# T8105.net
KiCad netlist of a schematic drawn in Altium Designer
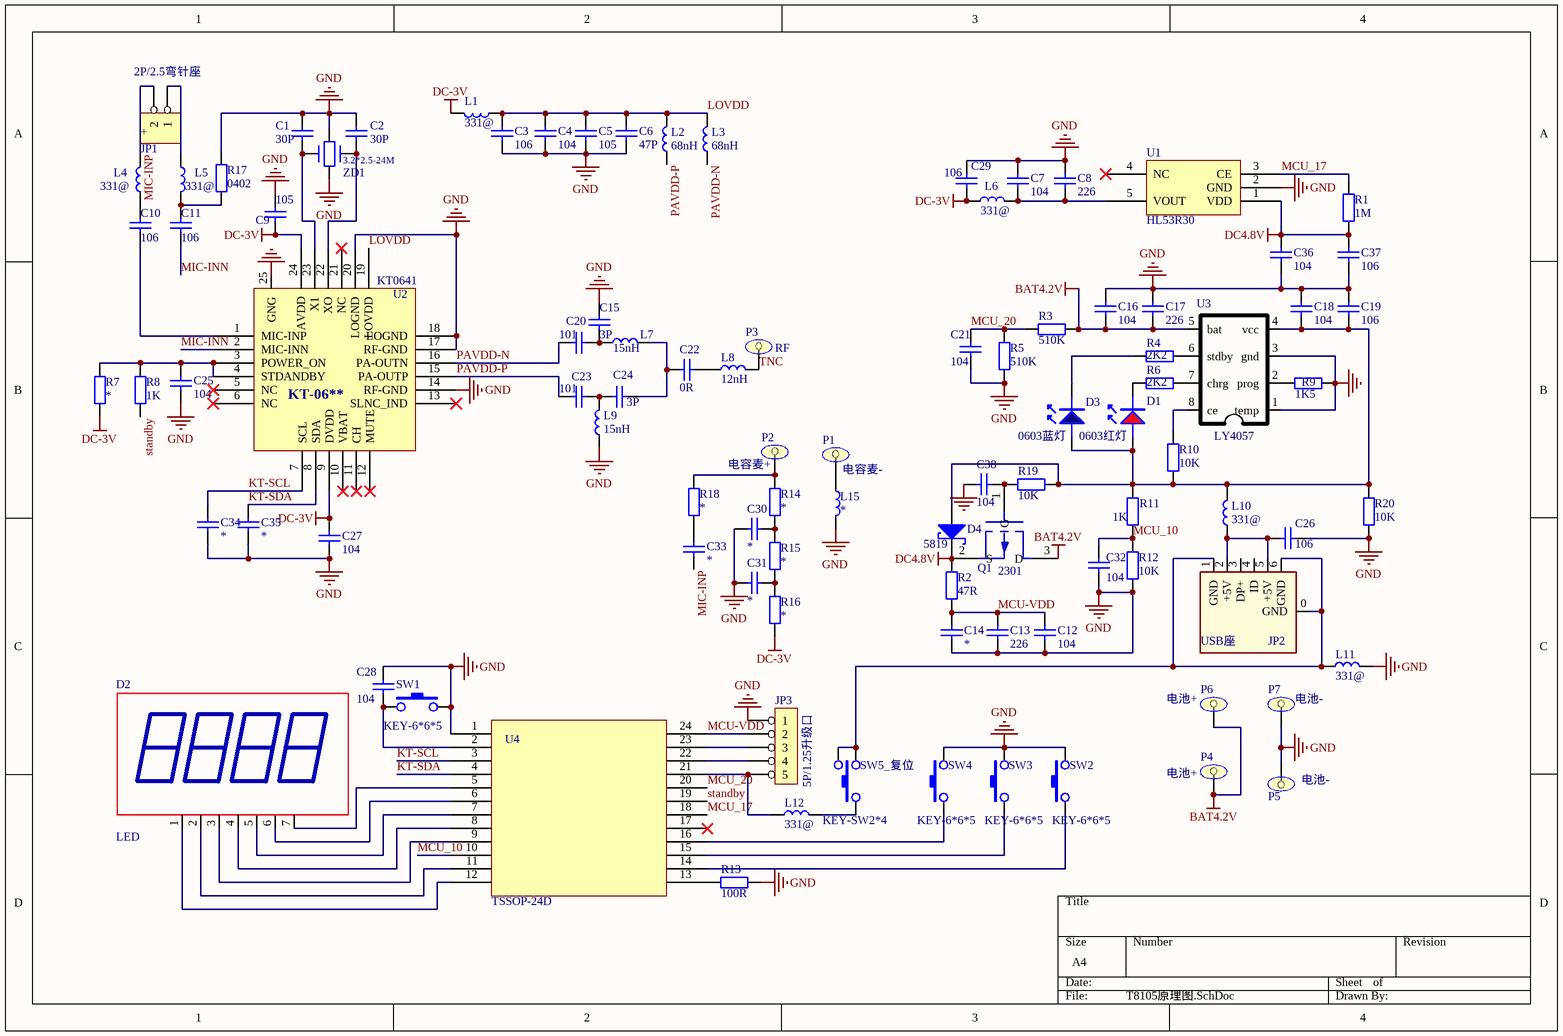
[diagram p0: T8105原理图.SchDoc]

(export (version "E")
  (design (tool "Eeschema 10.0.6"))
  (components
    (comp (ref "C1")
      (value "30P")
      (footprint "C0402")
      (description "贴片电容")
      (libsource (lib "CLR原理图封装库") (part "C0402"))
    )
    (comp (ref "C2")
      (value "30P")
      (footprint "C0402")
      (description "贴片电容")
      (libsource (lib "CLR原理图封装库") (part "C0402"))
    )
    (comp (ref "C3")
      (value "106")
      (footprint "C0603")
      (description "贴片电容")
      (libsource (lib "CLR原理图封装库") (part "C0603"))
    )
    (comp (ref "C4")
      (value "104")
      (footprint "C0402")
      (description "贴片电容")
      (libsource (lib "CLR原理图封装库") (part "C0402"))
    )
    (comp (ref "C5")
      (value "105")
      (footprint "C0402")
      (description "贴片电容")
      (libsource (lib "CLR原理图封装库") (part "C0402"))
    )
    (comp (ref "C6")
      (value "47P")
      (footprint "C0402")
      (description "贴片电容")
      (libsource (lib "CLR原理图封装库") (part "C0402"))
    )
    (comp (ref "C7")
      (value "104")
      (footprint "C0402")
      (description "贴片电容")
      (libsource (lib "CLR原理图封装库") (part "C0402"))
    )
    (comp (ref "C8")
      (value "226")
      (footprint "C0603")
      (description "贴片电容")
      (libsource (lib "CLR原理图封装库") (part "C0603"))
    )
    (comp (ref "C9")
      (value "105")
      (footprint "C0402")
      (description "贴片电容")
      (libsource (lib "CLR原理图封装库") (part "C0402"))
    )
    (comp (ref "C10")
      (value "106")
      (footprint "C0603")
      (description "贴片电容")
      (libsource (lib "CLR原理图封装库") (part "C0603"))
    )
    (comp (ref "C11")
      (value "106")
      (footprint "C0603")
      (description "贴片电容")
      (libsource (lib "CLR原理图封装库") (part "C0603"))
    )
    (comp (ref "C12")
      (value "104")
      (footprint "C0402")
      (description "贴片电容")
      (libsource (lib "CLR原理图封装库") (part "C0402"))
    )
    (comp (ref "C13")
      (value "226")
      (footprint "C0603")
      (description "贴片电容")
      (libsource (lib "CLR原理图封装库") (part "C0603"))
    )
    (comp (ref "C14")
      (value "*")
      (footprint "C1206")
      (description "贴片电容")
      (libsource (lib "CLR原理图封装库") (part "C1206"))
    )
    (comp (ref "C15")
      (value "3P")
      (footprint "C0402")
      (description "贴片电容")
      (libsource (lib "CLR原理图封装库") (part "C0402"))
    )
    (comp (ref "C16")
      (value "104")
      (footprint "C0402")
      (description "贴片电容")
      (libsource (lib "CLR原理图封装库") (part "C0402"))
    )
    (comp (ref "C17")
      (value "226")
      (footprint "C0603")
      (description "贴片电容")
      (libsource (lib "CLR原理图封装库") (part "C0603"))
    )
    (comp (ref "C18")
      (value "104")
      (footprint "C0402")
      (description "贴片电容")
      (libsource (lib "CLR原理图封装库") (part "C0402"))
    )
    (comp (ref "C19")
      (value "106")
      (footprint "C0603")
      (description "贴片电容")
      (libsource (lib "CLR原理图封装库") (part "C0603"))
    )
    (comp (ref "C20")
      (value "101")
      (footprint "C0402")
      (description "贴片电容")
      (libsource (lib "CLR原理图封装库") (part "C0402"))
    )
    (comp (ref "C21")
      (value "104")
      (footprint "C0402")
      (description "贴片电容")
      (libsource (lib "CLR原理图封装库") (part "C0402"))
    )
    (comp (ref "C22")
      (value "0R")
      (footprint "C0402")
      (description "贴片电容")
      (libsource (lib "CLR原理图封装库") (part "C0402"))
    )
    (comp (ref "C23")
      (value "101")
      (footprint "C0402")
      (description "贴片电容")
      (libsource (lib "CLR原理图封装库") (part "C0402"))
    )
    (comp (ref "C24")
      (value "3P")
      (footprint "C0402")
      (description "贴片电容")
      (libsource (lib "CLR原理图封装库") (part "C0402"))
    )
    (comp (ref "C25")
      (value "104")
      (footprint "C0402")
      (description "贴片电容")
      (libsource (lib "CLR原理图封装库") (part "C0402"))
    )
    (comp (ref "C26")
      (value "106")
      (footprint "C0603")
      (description "贴片电容")
      (libsource (lib "CLR原理图封装库") (part "C0603"))
    )
    (comp (ref "C27")
      (value "104")
      (footprint "C0402")
      (description "贴片电容")
      (libsource (lib "CLR原理图封装库") (part "C0402"))
    )
    (comp (ref "C28")
      (value "104")
      (footprint "C0402")
      (description "贴片电容")
      (libsource (lib "CLR原理图封装库") (part "C0402"))
    )
    (comp (ref "C29")
      (value "106")
      (footprint "C0603")
      (description "贴片电容")
      (libsource (lib "CLR原理图封装库") (part "C0603"))
    )
    (comp (ref "C30")
      (value "*")
      (footprint "C0603")
      (description "贴片电容")
      (libsource (lib "CLR原理图封装库") (part "C0603"))
    )
    (comp (ref "C31")
      (value "*")
      (footprint "C0603")
      (description "贴片电容")
      (libsource (lib "CLR原理图封装库") (part "C0603"))
    )
    (comp (ref "C32")
      (value "104")
      (footprint "C0402")
      (description "贴片电容")
      (libsource (lib "CLR原理图封装库") (part "C0402"))
    )
    (comp (ref "C33")
      (value "*")
      (footprint "C0603")
      (description "贴片电容")
      (libsource (lib "CLR原理图封装库") (part "C0603"))
    )
    (comp (ref "C34")
      (value "*")
      (footprint "C0402")
      (description "贴片电容")
      (libsource (lib "CLR原理图封装库") (part "C0402"))
    )
    (comp (ref "C35")
      (value "*")
      (footprint "C0402")
      (description "贴片电容")
      (libsource (lib "CLR原理图封装库") (part "C0402"))
    )
    (comp (ref "C36")
      (value "104")
      (footprint "C0402")
      (description "贴片电容")
      (libsource (lib "CLR原理图封装库") (part "C0402"))
    )
    (comp (ref "C37")
      (value "106")
      (footprint "C0603")
      (description "贴片电容")
      (libsource (lib "CLR原理图封装库") (part "C0603"))
    )
    (comp (ref "C38")
      (value "104")
      (footprint "C0402")
      (description "贴片电容")
      (libsource (lib "CLR原理图封装库") (part "C0402"))
    )
    (comp (ref "D1")
      (value "0603红灯")
      (footprint "LED-0603")
      (description "贴片LED")
      (libsource (lib "CLR原理图封装库") (part "LED-0603"))
    )
    (comp (ref "D2")
      (value "LED")
      (footprint "LED-15*16*7-7pin")
      (description "数码管")
      (libsource (lib "CLR原理图封装库") (part "LED-15*16/数码管"))
    )
    (comp (ref "D3")
      (value "0603蓝灯")
      (footprint "LED-0603")
      (description "贴片LED")
      (libsource (lib "CLR原理图封装库") (part "LED-0603_蓝"))
    )
    (comp (ref "D4")
      (value "5819")
      (footprint "SOD-123")
      (description "贴片肖特基二极管")
      (libsource (lib "CLR原理图封装库") (part "SOD-123"))
    )
    (comp (ref "JP1")
      (value "2P/2.5弯针座")
      (footprint "2P针座-2.54MM_弯针")
      (description "直插针座")
      (libsource (lib "CLR原理图封装库") (part "2P/2.5弯针座"))
    )
    (comp (ref "JP2")
      (value "USB座")
      (footprint "USB-TYPE-C3.1-6")
      (description "直插USB充电座")
      (libsource (lib "CLR原理图封装库") (part "USB-TYPE-C3.1-6"))
    )
    (comp (ref "JP3")
      (value "5P/1.25升级口")
      (footprint "5P插针-12.5MM")
      (description "直插插针")
      (libsource (lib "CLR原理图封装库") (part "5P/1.25插针"))
    )
    (comp (ref "L1")
      (value "331@")
      (footprint "L0402")
      (description "贴片电感")
      (libsource (lib "CLR原理图封装库") (part "L0402"))
    )
    (comp (ref "L2")
      (value "68nH")
      (footprint "L0603")
      (description "贴片电感")
      (libsource (lib "CLR原理图封装库") (part "L0603"))
    )
    (comp (ref "L3")
      (value "68nH")
      (footprint "L0402")
      (description "贴片电感")
      (libsource (lib "CLR原理图封装库") (part "L0402"))
    )
    (comp (ref "L4")
      (value "331@")
      (footprint "L0402")
      (description "贴片电感")
      (libsource (lib "CLR原理图封装库") (part "L0402"))
    )
    (comp (ref "L5")
      (value "331@")
      (footprint "L0402")
      (description "贴片电感")
      (libsource (lib "CLR原理图封装库") (part "L0402"))
    )
    (comp (ref "L6")
      (value "331@")
      (footprint "L0402")
      (description "贴片电感")
      (libsource (lib "CLR原理图封装库") (part "L0402"))
    )
    (comp (ref "L7")
      (value "15nH")
      (footprint "L0402")
      (description "贴片电感")
      (libsource (lib "CLR原理图封装库") (part "L0402"))
    )
    (comp (ref "L8")
      (value "12nH")
      (footprint "L0402")
      (description "贴片电感")
      (libsource (lib "CLR原理图封装库") (part "L0402"))
    )
    (comp (ref "L9")
      (value "15nH")
      (footprint "L0402")
      (description "贴片电感")
      (libsource (lib "CLR原理图封装库") (part "L0402"))
    )
    (comp (ref "L10")
      (value "331@")
      (footprint "L0805")
      (description "贴片电感")
      (libsource (lib "CLR原理图封装库") (part "L0805"))
    )
    (comp (ref "L11")
      (value "331@")
      (footprint "L0805")
      (description "贴片电感")
      (libsource (lib "CLR原理图封装库") (part "L0805"))
    )
    (comp (ref "L12")
      (value "331@")
      (footprint "L0402")
      (description "贴片电感")
      (libsource (lib "CLR原理图封装库") (part "L0402"))
    )
    (comp (ref "L15")
      (value "*")
      (footprint "L0603")
      (description "贴片电感")
      (libsource (lib "CLR原理图封装库") (part "L0603"))
    )
    (comp (ref "P1")
      (value "电容麦-")
      (footprint "2.2mm焊盘")
      (description "测试焊盘")
      (libsource (lib "") (part "测试焊点_1"))
    )
    (comp (ref "P2")
      (value "电容麦+")
      (footprint "2.2mm焊盘")
      (description "测试焊盘")
      (libsource (lib "") (part "测试焊点_1"))
    )
    (comp (ref "P3")
      (value "RF")
      (footprint "2.2mm焊盘")
      (description "测试焊盘")
      (libsource (lib "") (part "测试焊点_1"))
    )
    (comp (ref "P4")
      (value "电池+")
      (footprint "2.2mm焊盘")
      (description "测试焊盘")
      (libsource (lib "") (part "测试焊点_1"))
    )
    (comp (ref "P5")
      (value "电池-")
      (footprint "2.2mm焊盘")
      (description "测试焊盘")
      (libsource (lib "CLR原理图封装库") (part "测试焊点"))
    )
    (comp (ref "P6")
      (value "电池+")
      (footprint "2.2mm焊盘")
      (description "测试焊盘")
      (libsource (lib "") (part "测试焊点_1"))
    )
    (comp (ref "P7")
      (value "电池-")
      (footprint "2.2mm焊盘")
      (description "测试焊盘")
      (libsource (lib "") (part "测试焊点_1"))
    )
    (comp (ref "Q1")
      (value "2301")
      (footprint "SOT-23-3")
      (description "贴片MOS三极管")
      (libsource (lib "CLR原理图封装库") (part "SOT-23-MOS"))
    )
    (comp (ref "R1")
      (value "1M")
      (footprint "R0402")
      (description "贴片电阻")
      (libsource (lib "") (part "R0402_2"))
    )
    (comp (ref "R2")
      (value "47R")
      (footprint "R0402")
      (description "贴片电阻")
      (libsource (lib "") (part "R0402_3"))
    )
    (comp (ref "R3")
      (value "510K")
      (footprint "R0402")
      (description "贴片电阻")
      (libsource (lib "CLR原理图封装库") (part "R0402"))
    )
    (comp (ref "R4")
      (value "2K2")
      (footprint "R0402")
      (description "贴片电阻")
      (libsource (lib "") (part "R0402_1"))
    )
    (comp (ref "R5")
      (value "510K")
      (footprint "R0402")
      (description "贴片电阻")
      (libsource (lib "") (part "R0402_2"))
    )
    (comp (ref "R6")
      (value "2K2")
      (footprint "R0402")
      (description "贴片电阻")
      (libsource (lib "") (part "R0402_1"))
    )
    (comp (ref "R7")
      (value "*")
      (footprint "R0402")
      (description "贴片电阻")
      (libsource (lib "") (part "R0402_3"))
    )
    (comp (ref "R8")
      (value "1K")
      (footprint "R0402")
      (description "贴片电阻")
      (libsource (lib "") (part "R0402_2"))
    )
    (comp (ref "R9")
      (value "1K5")
      (footprint "R0402")
      (description "贴片电阻")
      (libsource (lib "CLR原理图封装库") (part "R0402"))
    )
    (comp (ref "R10")
      (value "10K")
      (footprint "R0402")
      (description "贴片电阻")
      (libsource (lib "") (part "R0402_2"))
    )
    (comp (ref "R11")
      (value "1K")
      (footprint "R0402")
      (description "贴片电阻")
      (libsource (lib "") (part "R0402_2"))
    )
    (comp (ref "R12")
      (value "10K")
      (footprint "R0402")
      (description "贴片电阻")
      (libsource (lib "") (part "R0402_2"))
    )
    (comp (ref "R13")
      (value "100R")
      (footprint "R0402")
      (description "贴片电阻")
      (libsource (lib "") (part "R0402_1"))
    )
    (comp (ref "R14")
      (value "*")
      (footprint "R0402")
      (description "贴片电阻")
      (libsource (lib "") (part "R0402_2"))
    )
    (comp (ref "R15")
      (value "*")
      (footprint "R0402")
      (description "贴片电阻")
      (libsource (lib "") (part "R0402_2"))
    )
    (comp (ref "R16")
      (value "*")
      (footprint "R0402")
      (description "贴片电阻")
      (libsource (lib "") (part "R0402_3"))
    )
    (comp (ref "R17")
      (value "0402")
      (footprint "R0402")
      (description "贴片电阻")
      (libsource (lib "") (part "R0402_2"))
    )
    (comp (ref "R18")
      (value "*")
      (footprint "R0402")
      (description "贴片电阻")
      (libsource (lib "") (part "R0402_2"))
    )
    (comp (ref "R19")
      (value "10K")
      (footprint "R0402")
      (description "贴片电阻")
      (libsource (lib "") (part "R0402_1"))
    )
    (comp (ref "R20")
      (value "10K")
      (footprint "R0402")
      (description "贴片电阻")
      (libsource (lib "") (part "R0402_3"))
    )
    (comp (ref "SW1")
      (value "KEY-6*6*5")
      (footprint "KEY-6*6*5")
      (description "贴片按键")
      (libsource (lib "CLR原理图封装库") (part "KEY-6*6*5"))
    )
    (comp (ref "SW2")
      (value "KEY-6*6*5")
      (footprint "KEY-6*6*5")
      (description "贴片按键")
      (libsource (lib "CLR原理图封装库") (part "KEY-6*6*5"))
    )
    (comp (ref "SW3")
      (value "KEY-6*6*5")
      (footprint "KEY-6*6*5")
      (description "贴片按键")
      (libsource (lib "CLR原理图封装库") (part "KEY-6*6*5"))
    )
    (comp (ref "SW4")
      (value "KEY-6*6*5")
      (footprint "KEY-6*6*5")
      (description "贴片按键")
      (libsource (lib "CLR原理图封装库") (part "KEY-6*6*5"))
    )
    (comp (ref "SW5_复位")
      (value "KEY-SW2*4")
      (footprint "KEY_SW2X4")
      (description "贴片按键")
      (libsource (lib "CLR原理图封装库") (part "KEY-SW2*4"))
    )
    (comp (ref "U1")
      (value "HL53R30")
      (footprint "SOT-23-5")
      (description "贴片三极管")
      (libsource (lib "CLR原理图封装库") (part "SOT-23-5_HL53R33"))
    )
    (comp (ref "U2")
      (value "KT0641")
      (footprint "QFN-24脚-4X4X0.5P")
      (libsource (lib "QFN原理图封装库") (part "QFN-24-4X4X0.5（0642/43）"))
    )
    (comp (ref "U3")
      (value "LY4057")
      (footprint "SOP-8-150")
      (description "充电管理")
      (libsource (lib "CLR原理图封装库") (part "LY4057"))
    )
    (comp (ref "U4")
      (value "TSSOP-24D")
      (footprint "TSSOP-24")
      (description "贴片集成块")
      (libsource (lib "CLR原理图封装库") (part "TSSOP-24"))
    )
    (comp (ref "ZD1")
      (value "3.2*2.5-24M")
      (footprint "SMD-3.2*2.5")
      (description "贴片晶振")
      (libsource (lib "CLR原理图封装库") (part "ZD-3.2*2.5"))
    )
  )
  (nets
    (net (code "1") (name "/KT-SCL") (class "Default")
      (node (ref "C34") (pin "2") (pinfunction "2_2") (pintype "passive"))
      (node (ref "U2") (pin "7") (pinfunction "SCL_7") (pintype "passive"))
      (node (ref "U4") (pin "3") (pintype "passive"))
    )
    (net (code "2") (name "/KT-SDA") (class "Default")
      (node (ref "C35") (pin "2") (pinfunction "2_2") (pintype "passive"))
      (node (ref "U2") (pin "8") (pinfunction "SDA_8") (pintype "passive"))
      (node (ref "U4") (pin "4") (pintype "passive"))
    )
    (net (code "3") (name "/LOVDD") (class "Default")
      (node (ref "C3") (pin "1") (pinfunction "1_1") (pintype "passive"))
      (node (ref "C4") (pin "2") (pinfunction "2_2") (pintype "passive"))
      (node (ref "C5") (pin "1") (pinfunction "1_1") (pintype "passive"))
      (node (ref "C6") (pin "1") (pinfunction "1_1") (pintype "passive"))
      (node (ref "L1") (pin "1") (pinfunction "1_1") (pintype "passive"))
      (node (ref "L2") (pin "2") (pinfunction "2_2") (pintype "passive"))
      (node (ref "L3") (pin "2") (pinfunction "2_2") (pintype "passive"))
      (node (ref "U2") (pin "19") (pinfunction "LOVDD_19") (pintype "passive"))
    )
    (net (code "4") (name "/MCU-VDD") (class "Default")
      (node (ref "C12") (pin "2") (pinfunction "2_2") (pintype "passive"))
      (node (ref "C13") (pin "2") (pinfunction "2_2") (pintype "passive"))
      (node (ref "C14") (pin "2") (pinfunction "2_2") (pintype "passive"))
      (node (ref "JP3") (pin "2") (pinfunction "2_2") (pintype "passive"))
      (node (ref "R2") (pin "2") (pinfunction "2_2") (pintype "passive"))
      (node (ref "U4") (pin "24") (pintype "passive"))
    )
    (net (code "5") (name "/MCU_10") (class "Default")
      (node (ref "C32") (pin "2") (pinfunction "2_2") (pintype "passive"))
      (node (ref "R11") (pin "1") (pinfunction "1_1") (pintype "passive"))
      (node (ref "R12") (pin "2") (pinfunction "2_2") (pintype "passive"))
      (node (ref "U4") (pin "10") (pintype "passive"))
    )
    (net (code "6") (name "/MCU_17") (class "Default")
      (node (ref "R1") (pin "2") (pinfunction "2_2") (pintype "passive"))
      (node (ref "U1") (pin "3") (pinfunction "CE_3") (pintype "passive"))
      (node (ref "U4") (pin "18") (pintype "passive"))
    )
    (net (code "7") (name "/MCU_20") (class "Default")
      (node (ref "C21") (pin "2") (pinfunction "2_2") (pintype "passive"))
      (node (ref "R3") (pin "2") (pinfunction "2_2") (pintype "passive"))
      (node (ref "R5") (pin "2") (pinfunction "2_2") (pintype "passive"))
      (node (ref "U4") (pin "20") (pintype "passive"))
    )
    (net (code "8") (name "/MIC-INN") (class "Default")
      (node (ref "C11") (pin "1") (pinfunction "1_1") (pintype "passive"))
      (node (ref "U2") (pin "2") (pinfunction "MIC-INN_2") (pintype "passive"))
    )
    (net (code "9") (name "/MIC-INP") (class "Default")
      (node (ref "C33") (pin "1") (pinfunction "1_1") (pintype "passive"))
      (node (ref "JP1") (pin "2") (pinfunction "2_2") (pintype "passive"))
      (node (ref "L4") (pin "2") (pinfunction "2_2") (pintype "passive"))
    )
    (net (code "10") (name "/PAVDD-N") (class "Default")
      (node (ref "C20") (pin "2") (pinfunction "2_2") (pintype "passive"))
      (node (ref "L3") (pin "1") (pinfunction "1_1") (pintype "passive"))
      (node (ref "U2") (pin "16") (pinfunction "PA-OUTN_16") (pintype "passive"))
    )
    (net (code "11") (name "/PAVDD-P") (class "Default")
      (node (ref "C23") (pin "2") (pinfunction "2_2") (pintype "passive"))
      (node (ref "L2") (pin "1") (pinfunction "1_1") (pintype "passive"))
      (node (ref "U2") (pin "15") (pinfunction "PA-OUTP_15") (pintype "passive"))
    )
    (net (code "12") (name "/TNC") (class "Default")
      (node (ref "L8") (pin "2") (pinfunction "2_2") (pintype "passive"))
      (node (ref "P3") (pin "1") (pinfunction "1_1") (pintype "passive"))
    )
    (net (code "13") (name "/standby") (class "Default")
      (node (ref "R8") (pin "1") (pinfunction "1_1") (pintype "passive"))
      (node (ref "U4") (pin "19") (pintype "passive"))
    )
    (net (code "14") (name "BAT4.2V") (class "Default")
      (node (ref "C16") (pin "1") (pinfunction "1_1") (pintype "passive"))
      (node (ref "C17") (pin "1") (pinfunction "1_1") (pintype "passive"))
      (node (ref "P4") (pin "1") (pinfunction "1_1") (pintype "passive"))
      (node (ref "P6") (pin "1") (pinfunction "1_1") (pintype "passive"))
      (node (ref "Q1") (pin "3") (pinfunction "D_3") (pintype "passive"))
      (node (ref "R3") (pin "1") (pinfunction "1_1") (pintype "passive"))
      (node (ref "U3") (pin "5") (pinfunction "bat_5") (pintype "passive"))
    )
    (net (code "15") (name "DC-3V") (class "Default")
      (node (ref "C27") (pin "2") (pinfunction "2_2") (pintype "passive"))
      (node (ref "C29") (pin "1") (pinfunction "1_1") (pintype "passive"))
      (node (ref "C9") (pin "2") (pinfunction "2_2") (pintype "passive"))
      (node (ref "L1") (pin "2") (pinfunction "2_2") (pintype "passive"))
      (node (ref "L6") (pin "1") (pinfunction "1_1") (pintype "passive"))
      (node (ref "R16") (pin "2") (pinfunction "2_2") (pintype "passive"))
      (node (ref "R7") (pin "2") (pinfunction "2_2") (pintype "passive"))
      (node (ref "U2") (pin "24") (pinfunction "AVDD_24") (pintype "passive"))
      (node (ref "U2") (pin "9") (pinfunction "DVDD_9") (pintype "passive"))
    )
    (net (code "16") (name "DC4.8V") (class "Default")
      (node (ref "C36") (pin "1") (pinfunction "1_1") (pintype "passive"))
      (node (ref "C37") (pin "2") (pinfunction "2_2") (pintype "passive"))
      (node (ref "D4") (pin "2") (pinfunction "K_2") (pintype "passive"))
      (node (ref "Q1") (pin "2") (pinfunction "S_2") (pintype "passive"))
      (node (ref "R1") (pin "1") (pinfunction "1_1") (pintype "passive"))
      (node (ref "R2") (pin "1") (pinfunction "1_1") (pintype "passive"))
      (node (ref "U1") (pin "1") (pinfunction "VDD_1") (pintype "passive"))
    )
    (net (code "17") (name "GND") (class "Default")
      (node (ref "C1") (pin "2") (pinfunction "2_2") (pintype "passive"))
      (node (ref "C12") (pin "1") (pinfunction "1_1") (pintype "passive"))
      (node (ref "C13") (pin "1") (pinfunction "1_1") (pintype "passive"))
      (node (ref "C14") (pin "1") (pinfunction "1_1") (pintype "passive"))
      (node (ref "C15") (pin "1") (pinfunction "1_1") (pintype "passive"))
      (node (ref "C16") (pin "2") (pinfunction "2_2") (pintype "passive"))
      (node (ref "C17") (pin "2") (pinfunction "2_2") (pintype "passive"))
      (node (ref "C18") (pin "2") (pinfunction "2_2") (pintype "passive"))
      (node (ref "C19") (pin "2") (pinfunction "2_2") (pintype "passive"))
      (node (ref "C2") (pin "2") (pinfunction "2_2") (pintype "passive"))
      (node (ref "C21") (pin "1") (pinfunction "1_1") (pintype "passive"))
      (node (ref "C25") (pin "2") (pinfunction "2_2") (pintype "passive"))
      (node (ref "C26") (pin "2") (pinfunction "2_2") (pintype "passive"))
      (node (ref "C27") (pin "1") (pinfunction "1_1") (pintype "passive"))
      (node (ref "C28") (pin "2") (pinfunction "2_2") (pintype "passive"))
      (node (ref "C29") (pin "2") (pinfunction "2_2") (pintype "passive"))
      (node (ref "C3") (pin "2") (pinfunction "2_2") (pintype "passive"))
      (node (ref "C30") (pin "1") (pinfunction "1_1") (pintype "passive"))
      (node (ref "C31") (pin "1") (pinfunction "1_1") (pintype "passive"))
      (node (ref "C32") (pin "1") (pinfunction "1_1") (pintype "passive"))
      (node (ref "C34") (pin "1") (pinfunction "1_1") (pintype "passive"))
      (node (ref "C35") (pin "1") (pinfunction "1_1") (pintype "passive"))
      (node (ref "C36") (pin "2") (pinfunction "2_2") (pintype "passive"))
      (node (ref "C37") (pin "1") (pinfunction "1_1") (pintype "passive"))
      (node (ref "C38") (pin "1") (pinfunction "1_1") (pintype "passive"))
      (node (ref "C4") (pin "1") (pinfunction "1_1") (pintype "passive"))
      (node (ref "C5") (pin "2") (pinfunction "2_2") (pintype "passive"))
      (node (ref "C6") (pin "2") (pinfunction "2_2") (pintype "passive"))
      (node (ref "C7") (pin "1") (pinfunction "1_1") (pintype "passive"))
      (node (ref "C8") (pin "2") (pinfunction "2_2") (pintype "passive"))
      (node (ref "C9") (pin "1") (pinfunction "1_1") (pintype "passive"))
      (node (ref "JP3") (pin "1") (pinfunction "1_1") (pintype "passive"))
      (node (ref "L11") (pin "2") (pinfunction "2_2") (pintype "passive"))
      (node (ref "L15") (pin "2") (pinfunction "2_2") (pintype "passive"))
      (node (ref "L9") (pin "1") (pinfunction "1_1") (pintype "passive"))
      (node (ref "P5") (pin "1") (pinfunction "1_1") (pintype "passive"))
      (node (ref "P7") (pin "1") (pinfunction "1_1") (pintype "passive"))
      (node (ref "R12") (pin "1") (pinfunction "1_1") (pintype "passive"))
      (node (ref "R13") (pin "2") (pinfunction "2_2") (pintype "passive"))
      (node (ref "R17") (pin "2") (pinfunction "2_2") (pintype "passive"))
      (node (ref "R20") (pin "2") (pinfunction "2_2") (pintype "passive"))
      (node (ref "R5") (pin "1") (pinfunction "1_1") (pintype "passive"))
      (node (ref "R9") (pin "1") (pinfunction "1_1") (pintype "passive"))
      (node (ref "SW1") (pin "2") (pinfunction "2_2") (pintype "passive"))
      (node (ref "SW2") (pin "2") (pinfunction "2_2") (pintype "passive"))
      (node (ref "SW3") (pin "2") (pinfunction "2_2") (pintype "passive"))
      (node (ref "SW4") (pin "2") (pinfunction "2_2") (pintype "passive"))
      (node (ref "U1") (pin "2") (pinfunction "GND_2") (pintype "passive"))
      (node (ref "U2") (pin "14") (pinfunction "RF-GND_14") (pintype "passive"))
      (node (ref "U2") (pin "17") (pinfunction "RF-GND_17") (pintype "passive"))
      (node (ref "U2") (pin "18") (pinfunction "LOGND_18") (pintype "passive"))
      (node (ref "U2") (pin "20") (pinfunction "LOGND_20") (pintype "passive"))
      (node (ref "U2") (pin "25") (pinfunction "GNG_25") (pintype "passive"))
      (node (ref "U3") (pin "1") (pinfunction "temp_1") (pintype "passive"))
      (node (ref "U3") (pin "3") (pinfunction "gnd_3") (pintype "passive"))
      (node (ref "U4") (pin "1") (pintype "passive"))
      (node (ref "ZD1") (pin "2") (pinfunction "2_2") (pintype "passive"))
      (node (ref "ZD1") (pin "4") (pinfunction "4_4") (pintype "passive"))
    )
    (net (code "18") (name "Net-(C10-Pad2)") (class "Default")
      (node (ref "C10") (pin "2") (pinfunction "2_2") (pintype "passive"))
      (node (ref "L4") (pin "1") (pinfunction "1_1") (pintype "passive"))
    )
    (net (code "19") (name "Net-(C11-Pad2)") (class "Default")
      (node (ref "C11") (pin "2") (pinfunction "2_2") (pintype "passive"))
      (node (ref "L5") (pin "2") (pinfunction "2_2") (pintype "passive"))
      (node (ref "R17") (pin "1") (pinfunction "1_1") (pintype "passive"))
    )
    (net (code "20") (name "Net-(C15-Pad2)") (class "Default")
      (node (ref "C15") (pin "2") (pinfunction "2_2") (pintype "passive"))
      (node (ref "C20") (pin "1") (pinfunction "1_1") (pintype "passive"))
      (node (ref "L7") (pin "1") (pinfunction "1_1") (pintype "passive"))
    )
    (net (code "21") (name "Net-(C22-Pad1)") (class "Default")
      (node (ref "C22") (pin "1") (pinfunction "1_1") (pintype "passive"))
      (node (ref "C24") (pin "2") (pinfunction "2_2") (pintype "passive"))
      (node (ref "L7") (pin "2") (pinfunction "2_2") (pintype "passive"))
    )
    (net (code "22") (name "Net-(C22-Pad2)") (class "Default")
      (node (ref "C22") (pin "2") (pinfunction "2_2") (pintype "passive"))
      (node (ref "L8") (pin "1") (pinfunction "1_1") (pintype "passive"))
    )
    (net (code "23") (name "Net-(C23-Pad1)") (class "Default")
      (node (ref "C23") (pin "1") (pinfunction "1_1") (pintype "passive"))
      (node (ref "C24") (pin "1") (pinfunction "1_1") (pintype "passive"))
      (node (ref "L9") (pin "2") (pinfunction "2_2") (pintype "passive"))
    )
    (net (code "24") (name "Net-(C26-Pad1)") (class "Default")
      (node (ref "C26") (pin "1") (pinfunction "1_1") (pintype "passive"))
      (node (ref "JP2") (pin "2") (pinfunction "+5V_2") (pintype "passive"))
      (node (ref "JP2") (pin "5") (pinfunction "+5V_5") (pintype "passive"))
      (node (ref "L10") (pin "1") (pinfunction "1_1") (pintype "passive"))
    )
    (net (code "25") (name "Net-(C28-Pad1)") (class "Default")
      (node (ref "C28") (pin "1") (pinfunction "1_1") (pintype "passive"))
      (node (ref "SW1") (pin "1") (pinfunction "1_1") (pintype "passive"))
      (node (ref "U4") (pin "2") (pintype "passive"))
    )
    (net (code "26") (name "Net-(C30-Pad2)") (class "Default")
      (node (ref "C30") (pin "2") (pinfunction "2_2") (pintype "passive"))
      (node (ref "R14") (pin "1") (pinfunction "1_1") (pintype "passive"))
      (node (ref "R15") (pin "2") (pinfunction "2_2") (pintype "passive"))
    )
    (net (code "27") (name "Net-(C31-Pad2)") (class "Default")
      (node (ref "C31") (pin "2") (pinfunction "2_2") (pintype "passive"))
      (node (ref "R15") (pin "1") (pinfunction "1_1") (pintype "passive"))
      (node (ref "R16") (pin "1") (pinfunction "1_1") (pintype "passive"))
    )
    (net (code "28") (name "Net-(C33-Pad2)") (class "Default")
      (node (ref "C33") (pin "2") (pinfunction "2_2") (pintype "passive"))
      (node (ref "R18") (pin "1") (pinfunction "1_1") (pintype "passive"))
    )
    (net (code "29") (name "Net-(D1-Pad2)") (class "Default")
      (node (ref "D1") (pin "2") (pinfunction "2_2") (pintype "passive"))
      (node (ref "R6") (pin "1") (pinfunction "1_1") (pintype "passive"))
    )
    (net (code "30") (name "Net-(D2-Pad1)") (class "Default")
      (node (ref "D2") (pin "1") (pintype "passive"))
      (node (ref "U4") (pin "12") (pintype "passive"))
    )
    (net (code "31") (name "Net-(D2-Pad2)") (class "Default")
      (node (ref "D2") (pin "2") (pintype "passive"))
      (node (ref "U4") (pin "11") (pintype "passive"))
    )
    (net (code "32") (name "Net-(D2-Pad3)") (class "Default")
      (node (ref "D2") (pin "3") (pintype "passive"))
      (node (ref "U4") (pin "9") (pintype "passive"))
    )
    (net (code "33") (name "Net-(D2-Pad4)") (class "Default")
      (node (ref "D2") (pin "4") (pintype "passive"))
      (node (ref "U4") (pin "8") (pintype "passive"))
    )
    (net (code "34") (name "Net-(D2-Pad5)") (class "Default")
      (node (ref "D2") (pin "5") (pintype "passive"))
      (node (ref "U4") (pin "7") (pintype "passive"))
    )
    (net (code "35") (name "Net-(D2-Pad6)") (class "Default")
      (node (ref "D2") (pin "6") (pintype "passive"))
      (node (ref "U4") (pin "6") (pintype "passive"))
    )
    (net (code "36") (name "Net-(D2-Pad7)") (class "Default")
      (node (ref "D2") (pin "7") (pintype "passive"))
      (node (ref "U4") (pin "5") (pintype "passive"))
    )
    (net (code "37") (name "Net-(D3-Pad2)") (class "Default")
      (node (ref "D3") (pin "2") (pinfunction "2_2") (pintype "passive"))
      (node (ref "R4") (pin "1") (pinfunction "1_1") (pintype "passive"))
    )
    (net (code "38") (name "Net-(D4-A)") (class "Default")
      (node (ref "C18") (pin "1") (pinfunction "1_1") (pintype "passive"))
      (node (ref "C19") (pin "1") (pinfunction "1_1") (pintype "passive"))
      (node (ref "D1") (pin "1") (pinfunction "1_1") (pintype "passive"))
      (node (ref "D3") (pin "1") (pinfunction "1_1") (pintype "passive"))
      (node (ref "D4") (pin "1") (pinfunction "A_1") (pintype "passive"))
      (node (ref "L10") (pin "2") (pinfunction "2_2") (pintype "passive"))
      (node (ref "R10") (pin "1") (pinfunction "1_1") (pintype "passive"))
      (node (ref "R11") (pin "2") (pinfunction "2_2") (pintype "passive"))
      (node (ref "R19") (pin "2") (pinfunction "2_2") (pintype "passive"))
      (node (ref "R20") (pin "1") (pinfunction "1_1") (pintype "passive"))
      (node (ref "U3") (pin "4") (pinfunction "vcc_4") (pintype "passive"))
    )
    (net (code "39") (name "Net-(JP1-Pad1)") (class "Default")
      (node (ref "JP1") (pin "1") (pinfunction "1_1") (pintype "passive"))
      (node (ref "L5") (pin "1") (pinfunction "1_1") (pintype "passive"))
    )
    (net (code "40") (name "Net-(JP2-GND-Pad0)") (class "Default")
      (node (ref "JP2") (pin "0") (pinfunction "GND_0") (pintype "passive"))
      (node (ref "JP2") (pin "1") (pinfunction "GND_1") (pintype "passive"))
      (node (ref "JP2") (pin "6") (pinfunction "GND_6") (pintype "passive"))
      (node (ref "L11") (pin "1") (pinfunction "1_1") (pintype "passive"))
      (node (ref "SW5_复位") (pin "2") (pinfunction "2_2") (pintype "passive"))
      (node (ref "SW5_复位") (pin "3") (pinfunction "3_3") (pintype "passive"))
    )
    (net (code "41") (name "Net-(JP3-Pad3)") (class "Default")
      (node (ref "JP3") (pin "3") (pinfunction "3_3") (pintype "passive"))
      (node (ref "U4") (pin "23") (pintype "passive"))
    )
    (net (code "42") (name "Net-(JP3-Pad4)") (class "Default")
      (node (ref "JP3") (pin "4") (pinfunction "4_4") (pintype "passive"))
      (node (ref "U4") (pin "22") (pintype "passive"))
    )
    (net (code "43") (name "Net-(JP3-Pad5)") (class "Default")
      (node (ref "JP3") (pin "5") (pinfunction "5_5") (pintype "passive"))
      (node (ref "L12") (pin "1") (pinfunction "1_1") (pintype "passive"))
      (node (ref "U4") (pin "21") (pintype "passive"))
    )
    (net (code "44") (name "Net-(L12-Pad2)") (class "Default")
      (node (ref "L12") (pin "2") (pinfunction "2_2") (pintype "passive"))
      (node (ref "SW5_复位") (pin "1") (pinfunction "1_1") (pintype "passive"))
    )
    (net (code "45") (name "Net-(L15-Pad1)") (class "Default")
      (node (ref "L15") (pin "1") (pinfunction "1_1") (pintype "passive"))
      (node (ref "P1") (pin "1") (pinfunction "1_1") (pintype "passive"))
    )
    (net (code "46") (name "Net-(P2-Pad1)") (class "Default")
      (node (ref "P2") (pin "1") (pinfunction "1_1") (pintype "passive"))
      (node (ref "R14") (pin "2") (pinfunction "2_2") (pintype "passive"))
      (node (ref "R18") (pin "2") (pinfunction "2_2") (pintype "passive"))
    )
    (net (code "47") (name "Net-(Q1-G)") (class "Default")
      (node (ref "C38") (pin "2") (pinfunction "2_2") (pintype "passive"))
      (node (ref "Q1") (pin "1") (pinfunction "G_1") (pintype "passive"))
      (node (ref "R19") (pin "1") (pinfunction "1_1") (pintype "passive"))
    )
    (net (code "48") (name "Net-(R13-Pad1)") (class "Default")
      (node (ref "R13") (pin "1") (pinfunction "1_1") (pintype "passive"))
      (node (ref "U4") (pin "13") (pintype "passive"))
    )
    (net (code "49") (name "Net-(SW2-Pad1)") (class "Default")
      (node (ref "SW2") (pin "1") (pinfunction "1_1") (pintype "passive"))
      (node (ref "U4") (pin "14") (pintype "passive"))
    )
    (net (code "50") (name "Net-(SW3-Pad1)") (class "Default")
      (node (ref "SW3") (pin "1") (pinfunction "1_1") (pintype "passive"))
      (node (ref "U4") (pin "15") (pintype "passive"))
    )
    (net (code "51") (name "Net-(SW4-Pad1)") (class "Default")
      (node (ref "SW4") (pin "1") (pinfunction "1_1") (pintype "passive"))
      (node (ref "U4") (pin "16") (pintype "passive"))
    )
    (net (code "52") (name "Net-(U1-VOUT)") (class "Default")
      (node (ref "C7") (pin "2") (pinfunction "2_2") (pintype "passive"))
      (node (ref "C8") (pin "1") (pinfunction "1_1") (pintype "passive"))
      (node (ref "L6") (pin "2") (pinfunction "2_2") (pintype "passive"))
      (node (ref "U1") (pin "5") (pinfunction "VOUT_5") (pintype "passive"))
    )
    (net (code "53") (name "Net-(U2-MIC-INP)") (class "Default")
      (node (ref "C10") (pin "1") (pinfunction "1_1") (pintype "passive"))
      (node (ref "U2") (pin "1") (pinfunction "MIC-INP_1") (pintype "passive"))
    )
    (net (code "54") (name "Net-(U2-POWER_ON)") (class "Default")
      (node (ref "C25") (pin "1") (pinfunction "1_1") (pintype "passive"))
      (node (ref "R7") (pin "1") (pinfunction "1_1") (pintype "passive"))
      (node (ref "R8") (pin "2") (pinfunction "2_2") (pintype "passive"))
      (node (ref "U2") (pin "3") (pinfunction "POWER_ON_3") (pintype "passive"))
      (node (ref "U2") (pin "4") (pinfunction "STDANDBY_4") (pintype "passive"))
    )
    (net (code "55") (name "Net-(U2-X1)") (class "Default")
      (node (ref "C1") (pin "1") (pinfunction "1_1") (pintype "passive"))
      (node (ref "U2") (pin "23") (pinfunction "X1_23") (pintype "passive"))
      (node (ref "ZD1") (pin "1") (pinfunction "1_1") (pintype "passive"))
    )
    (net (code "56") (name "Net-(U2-XO)") (class "Default")
      (node (ref "C2") (pin "1") (pinfunction "1_1") (pintype "passive"))
      (node (ref "U2") (pin "22") (pinfunction "XO_22") (pintype "passive"))
      (node (ref "ZD1") (pin "3") (pinfunction "3_3") (pintype "passive"))
    )
    (net (code "57") (name "Net-(U3-ce)") (class "Default")
      (node (ref "R10") (pin "2") (pinfunction "2_2") (pintype "passive"))
      (node (ref "U3") (pin "8") (pinfunction "ce_8") (pintype "passive"))
    )
    (net (code "58") (name "Net-(U3-chrg)") (class "Default")
      (node (ref "R6") (pin "2") (pinfunction "2_2") (pintype "passive"))
      (node (ref "U3") (pin "7") (pinfunction "chrg_7") (pintype "passive"))
    )
    (net (code "59") (name "Net-(U3-prog)") (class "Default")
      (node (ref "R9") (pin "2") (pinfunction "2_2") (pintype "passive"))
      (node (ref "U3") (pin "2") (pinfunction "prog_2") (pintype "passive"))
    )
    (net (code "60") (name "Net-(U3-stdby)") (class "Default")
      (node (ref "R4") (pin "2") (pinfunction "2_2") (pintype "passive"))
      (node (ref "U3") (pin "6") (pinfunction "stdby_6") (pintype "passive"))
    )
    (net (code "61") (name "unconnected-(JP2-DP+-Pad3)") (class "Default")
      (node (ref "JP2") (pin "3") (pinfunction "DP+_3") (pintype "passive"))
    )
    (net (code "62") (name "unconnected-(JP2-ID-Pad4)") (class "Default")
      (node (ref "JP2") (pin "4") (pinfunction "ID_4") (pintype "passive"))
    )
    (net (code "63") (name "unconnected-(U1-NC-Pad4)") (class "Default")
      (node (ref "U1") (pin "4") (pinfunction "NC_4") (pintype "passive+no_connect"))
    )
    (net (code "64") (name "unconnected-(U2-CH-Pad11)") (class "Default")
      (node (ref "U2") (pin "11") (pinfunction "CH_11") (pintype "passive+no_connect"))
    )
    (net (code "65") (name "unconnected-(U2-MUTE-Pad12)") (class "Default")
      (node (ref "U2") (pin "12") (pinfunction "MUTE_12") (pintype "passive+no_connect"))
    )
    (net (code "66") (name "unconnected-(U2-NC-Pad5)") (class "Default")
      (node (ref "U2") (pin "5") (pinfunction "NC_5") (pintype "passive+no_connect"))
    )
    (net (code "67") (name "unconnected-(U2-NC-Pad6)") (class "Default")
      (node (ref "U2") (pin "6") (pinfunction "NC_6") (pintype "passive+no_connect"))
    )
    (net (code "68") (name "unconnected-(U2-NC-Pad21)") (class "Default")
      (node (ref "U2") (pin "21") (pinfunction "NC_21") (pintype "passive+no_connect"))
    )
    (net (code "69") (name "unconnected-(U2-SLNC_IND-Pad13)") (class "Default")
      (node (ref "U2") (pin "13") (pinfunction "SLNC_IND_13") (pintype "passive+no_connect"))
    )
    (net (code "70") (name "unconnected-(U2-VBAT-Pad10)") (class "Default")
      (node (ref "U2") (pin "10") (pinfunction "VBAT_10") (pintype "passive+no_connect"))
    )
    (net (code "71") (name "unconnected-(U4-Pad17)") (class "Default")
      (node (ref "U4") (pin "17") (pintype "passive+no_connect"))
    )
  )
)
